# sb-sonata-led.net
KiCad netlist of a schematic drawn in Altium Designer
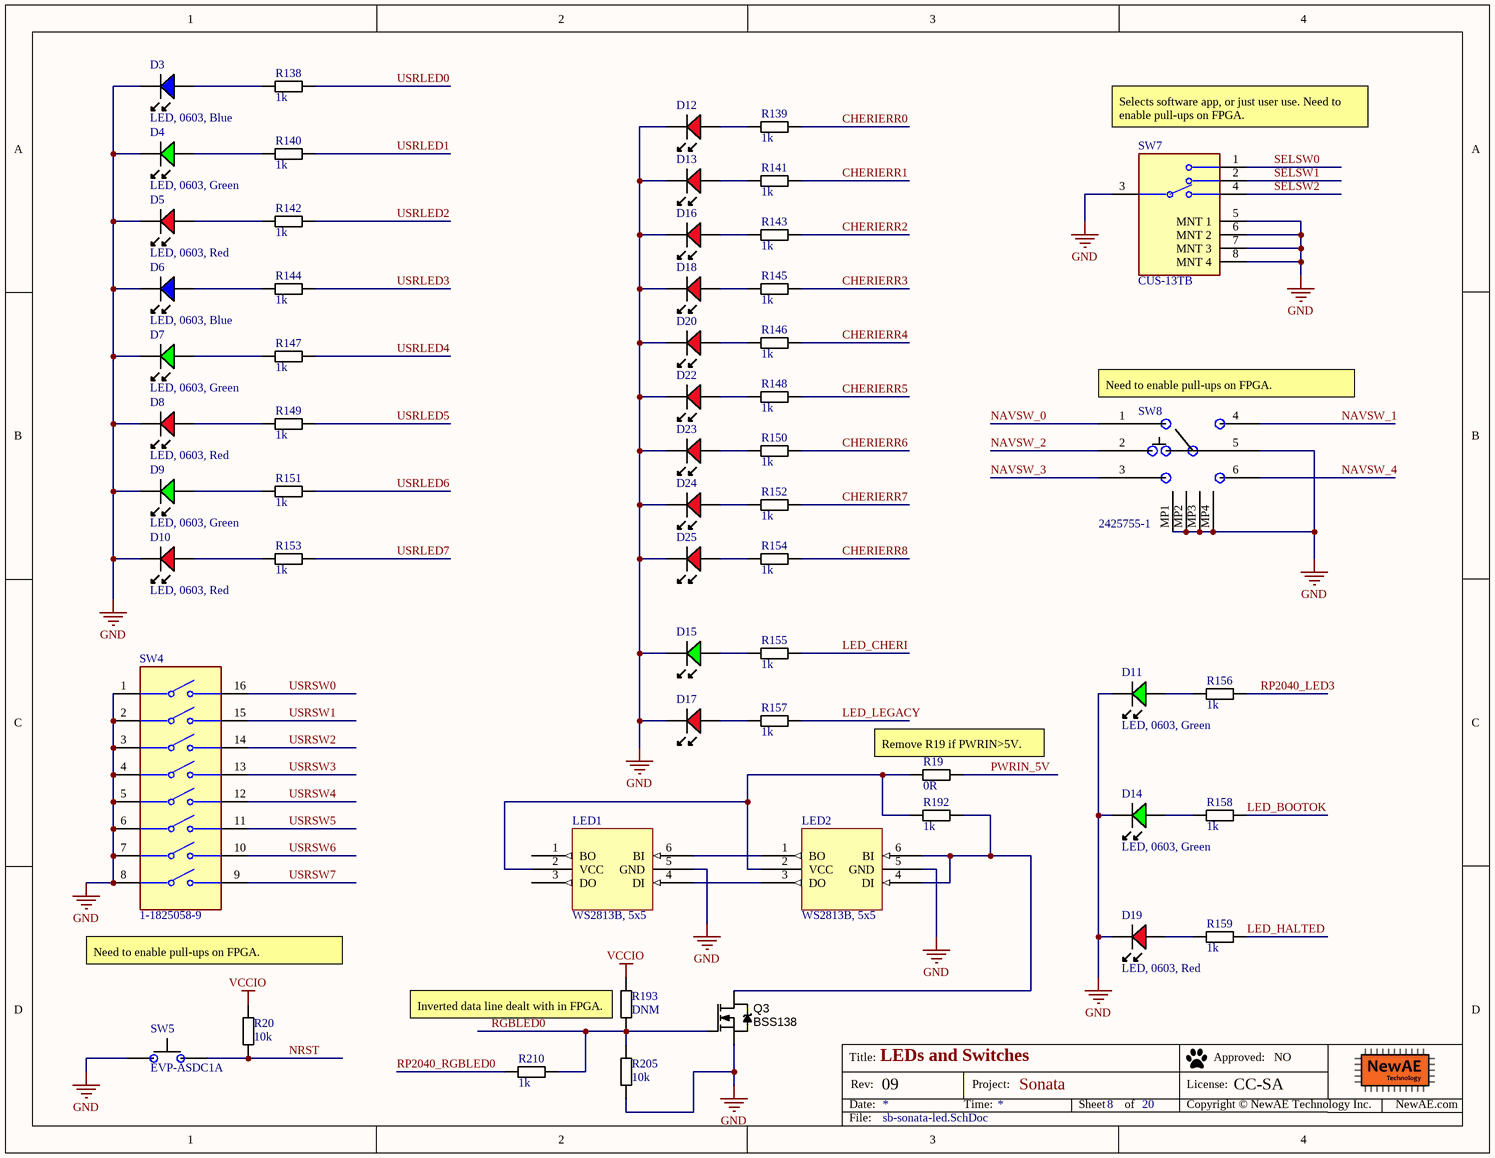
[diagram p0: sb-sonata-led.SchDoc]

(export (version "E")
  (design (tool "Eeschema 10.0.6"))
  (components
    (comp (ref "D3")
      (value "LED, 0603, Blue")
      (footprint "LED-0603-BLUE")
      (description "Chip LED, Blue")
      (fields (field (name "PART NUMBER") "LEDCHIP_0603_BLUE"))
      (libsource (lib "NewAE_AltiumLib") (part "LED_BLUE"))
    )
    (comp (ref "D4")
      (value "LED, 0603, Green")
      (footprint "LED-0603-GREEN")
      (description "Chip LED, Green")
      (fields (field (name "PART NUMBER") "LEDCHIP_0603_GREEN"))
      (libsource (lib "NewAE_AltiumLib") (part "LED_GREEN"))
    )
    (comp (ref "D5")
      (value "LED, 0603, Red")
      (footprint "LED-0603-RED")
      (description "Chip LED, Red")
      (fields (field (name "PART NUMBER") "LEDCHIP_0603_RED"))
      (libsource (lib "NewAE_AltiumLib") (part "LED_RED"))
    )
    (comp (ref "D6")
      (value "LED, 0603, Blue")
      (footprint "LED-0603-BLUE")
      (description "Chip LED, Blue")
      (fields (field (name "PART NUMBER") "LEDCHIP_0603_BLUE"))
      (libsource (lib "NewAE_AltiumLib") (part "LED_BLUE"))
    )
    (comp (ref "D7")
      (value "LED, 0603, Green")
      (footprint "LED-0603-GREEN")
      (description "Chip LED, Green")
      (fields (field (name "PART NUMBER") "LEDCHIP_0603_GREEN"))
      (libsource (lib "NewAE_AltiumLib") (part "LED_GREEN"))
    )
    (comp (ref "D8")
      (value "LED, 0603, Red")
      (footprint "LED-0603-RED")
      (description "Chip LED, Red")
      (fields (field (name "PART NUMBER") "LEDCHIP_0603_RED"))
      (libsource (lib "NewAE_AltiumLib") (part "LED_RED"))
    )
    (comp (ref "D9")
      (value "LED, 0603, Green")
      (footprint "LED-0603-GREEN")
      (description "Chip LED, Green")
      (fields (field (name "PART NUMBER") "LEDCHIP_0603_GREEN"))
      (libsource (lib "NewAE_AltiumLib") (part "LED_GREEN"))
    )
    (comp (ref "D10")
      (value "LED, 0603, Red")
      (footprint "LED-0603-RED")
      (description "Chip LED, Red")
      (fields (field (name "PART NUMBER") "LEDCHIP_0603_RED"))
      (libsource (lib "NewAE_AltiumLib") (part "LED_RED"))
    )
    (comp (ref "D11")
      (value "LED, 0603, Green")
      (footprint "LED-0603-GREEN")
      (description "Chip LED, Green")
      (fields (field (name "PART NUMBER") "LEDCHIP_0603_GREEN"))
      (libsource (lib "NewAE_AltiumLib") (part "LED_GREEN"))
    )
    (comp (ref "D12")
      (value "LED, 0603, Red")
      (footprint "LED-0603-RED")
      (description "Chip LED, Red")
      (fields (field (name "PART NUMBER") "LEDCHIP_0603_RED"))
      (libsource (lib "NewAE_AltiumLib") (part "LED_RED"))
    )
    (comp (ref "D13")
      (value "LED, 0603, Red")
      (footprint "LED-0603-RED")
      (description "Chip LED, Red")
      (fields (field (name "PART NUMBER") "LEDCHIP_0603_RED"))
      (libsource (lib "NewAE_AltiumLib") (part "LED_RED"))
    )
    (comp (ref "D14")
      (value "LED, 0603, Green")
      (footprint "LED-0603-GREEN")
      (description "Chip LED, Green")
      (fields (field (name "PART NUMBER") "LEDCHIP_0603_GREEN"))
      (libsource (lib "NewAE_AltiumLib") (part "LED_GREEN"))
    )
    (comp (ref "D15")
      (value "LED, 0603, Green")
      (footprint "LED-0603-GREEN")
      (description "Chip LED, Green")
      (fields (field (name "PART NUMBER") "LEDCHIP_0603_GREEN"))
      (libsource (lib "NewAE_AltiumLib") (part "LED_GREEN"))
    )
    (comp (ref "D16")
      (value "LED, 0603, Red")
      (footprint "LED-0603-RED")
      (description "Chip LED, Red")
      (fields (field (name "PART NUMBER") "LEDCHIP_0603_RED"))
      (libsource (lib "NewAE_AltiumLib") (part "LED_RED"))
    )
    (comp (ref "D17")
      (value "LED, 0603, Red")
      (footprint "LED-0603-RED")
      (description "Chip LED, Red")
      (fields (field (name "PART NUMBER") "LEDCHIP_0603_RED"))
      (libsource (lib "NewAE_AltiumLib") (part "LED_RED"))
    )
    (comp (ref "D18")
      (value "LED, 0603, Red")
      (footprint "LED-0603-RED")
      (description "Chip LED, Red")
      (fields (field (name "PART NUMBER") "LEDCHIP_0603_RED"))
      (libsource (lib "NewAE_AltiumLib") (part "LED_RED"))
    )
    (comp (ref "D19")
      (value "LED, 0603, Red")
      (footprint "LED-0603-RED")
      (description "Chip LED, Red")
      (fields (field (name "PART NUMBER") "LEDCHIP_0603_RED"))
      (libsource (lib "NewAE_AltiumLib") (part "LED_RED"))
    )
    (comp (ref "D20")
      (value "LED, 0603, Red")
      (footprint "LED-0603-RED")
      (description "Chip LED, Red")
      (fields (field (name "PART NUMBER") "LEDCHIP_0603_RED"))
      (libsource (lib "NewAE_AltiumLib") (part "LED_RED"))
    )
    (comp (ref "D22")
      (value "LED, 0603, Red")
      (footprint "LED-0603-RED")
      (description "Chip LED, Red")
      (fields (field (name "PART NUMBER") "LEDCHIP_0603_RED"))
      (libsource (lib "NewAE_AltiumLib") (part "LED_RED"))
    )
    (comp (ref "D23")
      (value "LED, 0603, Red")
      (footprint "LED-0603-RED")
      (description "Chip LED, Red")
      (fields (field (name "PART NUMBER") "LEDCHIP_0603_RED"))
      (libsource (lib "NewAE_AltiumLib") (part "LED_RED"))
    )
    (comp (ref "D24")
      (value "LED, 0603, Red")
      (footprint "LED-0603-RED")
      (description "Chip LED, Red")
      (fields (field (name "PART NUMBER") "LEDCHIP_0603_RED"))
      (libsource (lib "NewAE_AltiumLib") (part "LED_RED"))
    )
    (comp (ref "D25")
      (value "LED, 0603, Red")
      (footprint "LED-0603-RED")
      (description "Chip LED, Red")
      (fields (field (name "PART NUMBER") "LEDCHIP_0603_RED"))
      (libsource (lib "NewAE_AltiumLib") (part "LED_RED"))
    )
    (comp (ref "LED1")
      (value "WS2813B, 5x5")
      (footprint "WS2813B_5x5")
      (description "WS2813B, 5x5 SMD Neopixel")
      (fields (field (name "PART NUMBER") "WS2813B_5x5"))
      (libsource (lib "NewAE_AltiumLib") (part "WS2813B"))
    )
    (comp (ref "LED2")
      (value "WS2813B, 5x5")
      (footprint "WS2813B_5x5")
      (description "WS2813B, 5x5 SMD Neopixel")
      (fields (field (name "PART NUMBER") "WS2813B_5x5"))
      (libsource (lib "NewAE_AltiumLib") (part "WS2813B"))
    )
    (comp (ref "Q3")
      (value "BSS138")
      (footprint "SOT95P245X110-3M")
      (description "MOSFET N-CH 30V 2.2A SOT23-3")
      (libsource (lib "NewAE_AltiumLib") (part "MOSFET_N_GSD"))
    )
    (comp (ref "R19")
      (value "0R")
      (footprint "RESC1608X55N")
      (description "0R, 0603, 1/10W")
      (fields (field (name "PART NUMBER") "RCHIP-0R-0603") (field (name "TOLERANCE") "1%"))
      (libsource (lib "") (part "RES-EU_2"))
    )
    (comp (ref "R20")
      (value "10k")
      (footprint "RESC1005X40N")
      (description "10k res, 0402, 1%, 1/16W")
      (fields (field (name "PART NUMBER") "RCHIP-10K-0402") (field (name "TOLERANCE") "1%"))
      (libsource (lib "") (part "RES-EU_1"))
    )
    (comp (ref "R138")
      (value "1k")
      (footprint "RESC1005X40N")
      (description "1k res, 0402, 1%, 1/16W")
      (fields (field (name "PART NUMBER") "RCHIP-1K-0402") (field (name "TOLERANCE") "1%"))
      (libsource (lib "NewAE_AltiumLib") (part "RES-EU"))
    )
    (comp (ref "R139")
      (value "1k")
      (footprint "RESC1005X40N")
      (description "1k res, 0402, 1%, 1/16W")
      (fields (field (name "PART NUMBER") "RCHIP-1K-0402") (field (name "TOLERANCE") "1%"))
      (libsource (lib "NewAE_AltiumLib") (part "RES-EU"))
    )
    (comp (ref "R140")
      (value "1k")
      (footprint "RESC1005X40N")
      (description "1k res, 0402, 1%, 1/16W")
      (fields (field (name "PART NUMBER") "RCHIP-1K-0402") (field (name "TOLERANCE") "1%"))
      (libsource (lib "NewAE_AltiumLib") (part "RES-EU"))
    )
    (comp (ref "R141")
      (value "1k")
      (footprint "RESC1005X40N")
      (description "1k res, 0402, 1%, 1/16W")
      (fields (field (name "PART NUMBER") "RCHIP-1K-0402") (field (name "TOLERANCE") "1%"))
      (libsource (lib "NewAE_AltiumLib") (part "RES-EU"))
    )
    (comp (ref "R142")
      (value "1k")
      (footprint "RESC1005X40N")
      (description "1k res, 0402, 1%, 1/16W")
      (fields (field (name "PART NUMBER") "RCHIP-1K-0402") (field (name "TOLERANCE") "1%"))
      (libsource (lib "NewAE_AltiumLib") (part "RES-EU"))
    )
    (comp (ref "R143")
      (value "1k")
      (footprint "RESC1005X40N")
      (description "1k res, 0402, 1%, 1/16W")
      (fields (field (name "PART NUMBER") "RCHIP-1K-0402") (field (name "TOLERANCE") "1%"))
      (libsource (lib "NewAE_AltiumLib") (part "RES-EU"))
    )
    (comp (ref "R144")
      (value "1k")
      (footprint "RESC1005X40N")
      (description "1k res, 0402, 1%, 1/16W")
      (fields (field (name "PART NUMBER") "RCHIP-1K-0402") (field (name "TOLERANCE") "1%"))
      (libsource (lib "NewAE_AltiumLib") (part "RES-EU"))
    )
    (comp (ref "R145")
      (value "1k")
      (footprint "RESC1005X40N")
      (description "1k res, 0402, 1%, 1/16W")
      (fields (field (name "PART NUMBER") "RCHIP-1K-0402") (field (name "TOLERANCE") "1%"))
      (libsource (lib "NewAE_AltiumLib") (part "RES-EU"))
    )
    (comp (ref "R146")
      (value "1k")
      (footprint "RESC1005X40N")
      (description "1k res, 0402, 1%, 1/16W")
      (fields (field (name "PART NUMBER") "RCHIP-1K-0402") (field (name "TOLERANCE") "1%"))
      (libsource (lib "NewAE_AltiumLib") (part "RES-EU"))
    )
    (comp (ref "R147")
      (value "1k")
      (footprint "RESC1005X40N")
      (description "1k res, 0402, 1%, 1/16W")
      (fields (field (name "PART NUMBER") "RCHIP-1K-0402") (field (name "TOLERANCE") "1%"))
      (libsource (lib "NewAE_AltiumLib") (part "RES-EU"))
    )
    (comp (ref "R148")
      (value "1k")
      (footprint "RESC1005X40N")
      (description "1k res, 0402, 1%, 1/16W")
      (fields (field (name "PART NUMBER") "RCHIP-1K-0402") (field (name "TOLERANCE") "1%"))
      (libsource (lib "NewAE_AltiumLib") (part "RES-EU"))
    )
    (comp (ref "R149")
      (value "1k")
      (footprint "RESC1005X40N")
      (description "1k res, 0402, 1%, 1/16W")
      (fields (field (name "PART NUMBER") "RCHIP-1K-0402") (field (name "TOLERANCE") "1%"))
      (libsource (lib "NewAE_AltiumLib") (part "RES-EU"))
    )
    (comp (ref "R150")
      (value "1k")
      (footprint "RESC1005X40N")
      (description "1k res, 0402, 1%, 1/16W")
      (fields (field (name "PART NUMBER") "RCHIP-1K-0402") (field (name "TOLERANCE") "1%"))
      (libsource (lib "NewAE_AltiumLib") (part "RES-EU"))
    )
    (comp (ref "R151")
      (value "1k")
      (footprint "RESC1005X40N")
      (description "1k res, 0402, 1%, 1/16W")
      (fields (field (name "PART NUMBER") "RCHIP-1K-0402") (field (name "TOLERANCE") "1%"))
      (libsource (lib "NewAE_AltiumLib") (part "RES-EU"))
    )
    (comp (ref "R152")
      (value "1k")
      (footprint "RESC1005X40N")
      (description "1k res, 0402, 1%, 1/16W")
      (fields (field (name "PART NUMBER") "RCHIP-1K-0402") (field (name "TOLERANCE") "1%"))
      (libsource (lib "NewAE_AltiumLib") (part "RES-EU"))
    )
    (comp (ref "R153")
      (value "1k")
      (footprint "RESC1005X40N")
      (description "1k res, 0402, 1%, 1/16W")
      (fields (field (name "PART NUMBER") "RCHIP-1K-0402") (field (name "TOLERANCE") "1%"))
      (libsource (lib "NewAE_AltiumLib") (part "RES-EU"))
    )
    (comp (ref "R154")
      (value "1k")
      (footprint "RESC1005X40N")
      (description "1k res, 0402, 1%, 1/16W")
      (fields (field (name "PART NUMBER") "RCHIP-1K-0402") (field (name "TOLERANCE") "1%"))
      (libsource (lib "NewAE_AltiumLib") (part "RES-EU"))
    )
    (comp (ref "R155")
      (value "1k")
      (footprint "RESC1005X40N")
      (description "1k res, 0402, 1%, 1/16W")
      (fields (field (name "PART NUMBER") "RCHIP-1K-0402") (field (name "TOLERANCE") "1%"))
      (libsource (lib "NewAE_AltiumLib") (part "RES-EU"))
    )
    (comp (ref "R156")
      (value "1k")
      (footprint "RESC1005X40N")
      (description "1k res, 0402, 1%, 1/16W")
      (fields (field (name "PART NUMBER") "RCHIP-1K-0402") (field (name "TOLERANCE") "1%"))
      (libsource (lib "NewAE_AltiumLib") (part "RES-EU"))
    )
    (comp (ref "R157")
      (value "1k")
      (footprint "RESC1005X40N")
      (description "1k res, 0402, 1%, 1/16W")
      (fields (field (name "PART NUMBER") "RCHIP-1K-0402") (field (name "TOLERANCE") "1%"))
      (libsource (lib "NewAE_AltiumLib") (part "RES-EU"))
    )
    (comp (ref "R158")
      (value "1k")
      (footprint "RESC1005X40N")
      (description "1k res, 0402, 1%, 1/16W")
      (fields (field (name "PART NUMBER") "RCHIP-1K-0402") (field (name "TOLERANCE") "1%"))
      (libsource (lib "NewAE_AltiumLib") (part "RES-EU"))
    )
    (comp (ref "R159")
      (value "1k")
      (footprint "RESC1005X40N")
      (description "1k res, 0402, 1%, 1/16W")
      (fields (field (name "PART NUMBER") "RCHIP-1K-0402") (field (name "TOLERANCE") "1%"))
      (libsource (lib "NewAE_AltiumLib") (part "RES-EU"))
    )
    (comp (ref "R192")
      (value "1k")
      (footprint "RESC1005X40N")
      (description "1k res, 0402, 1%, 1/16W")
      (fields (field (name "PART NUMBER") "RCHIP-1K-0402") (field (name "TOLERANCE") "1%"))
      (libsource (lib "") (part "RES-EU_2"))
    )
    (comp (ref "R193")
      (value "DNM")
      (footprint "RESC1005X40N")
      (fields (field (name "PART NUMBER") "RCHIP-DNM-0402"))
      (libsource (lib "") (part "RES-EU_1"))
    )
    (comp (ref "R205")
      (value "10k")
      (footprint "RESC1005X40N")
      (description "10k res, 0402, 1%, 1/16W")
      (fields (field (name "PART NUMBER") "RCHIP-10K-0402") (field (name "TOLERANCE") "1%"))
      (libsource (lib "") (part "RES-EU_1"))
    )
    (comp (ref "R210")
      (value "1k")
      (footprint "RESC1005X40N")
      (description "1k res, 0402, 1%, 1/16W")
      (fields (field (name "PART NUMBER") "RCHIP-1K-0402") (field (name "TOLERANCE") "1%"))
      (libsource (lib "NewAE_AltiumLib") (part "RES-EU"))
    )
    (comp (ref "SW4")
      (value "1-1825058-9")
      (footprint "FP-1-1825058-9-MFG")
      (description "SWITCH SLIDE DIP SPST 100MA 24V")
      (fields
        (field (name "MANUFACTURER") "TE Connectivity")
        (field (name "OCTOPART") "https://octopart.com/1-1825058-9-te+connectivity-46507285")
      )
      (libsource (lib "Altium Content Vault") (part "88b473189f0daa5e8e83a09a3141fee"))
    )
    (comp (ref "SW5")
      (value "EVP-ASDC1A")
      (footprint "EVPAS")
      (description "Pushbutton, SMD, 2.5NM force, NO")
      (libsource (lib "NewAE_AltiumLib") (part "SW_PB_NO_2PIN"))
    )
    (comp (ref "SW7")
      (value "CUS-13TB")
      (footprint "FP-CUS-13TB-MFG")
      (description "SWITCH SLIDE SP3T 300MA 4V")
      (libsource (lib "Altium Content Vault") (part "47bcb96ef67674530f45e4053201745"))
    )
    (comp (ref "SW8")
      (value "2425755-1")
      (footprint "2425755-1")
      (description "5-Way Joystick")
      (libsource (lib "NewAE_AltiumLib") (part "SW_5WAY_4MP"))
    )
  )
  (nets
    (net (code "1") (name "/CHERIERR0") (class "Default")
      (node (ref "R139") (pin "1") (pinfunction "1_1") (pintype "passive"))
    )
    (net (code "2") (name "/CHERIERR1") (class "Default")
      (node (ref "R141") (pin "1") (pinfunction "1_1") (pintype "passive"))
    )
    (net (code "3") (name "/CHERIERR2") (class "Default")
      (node (ref "R143") (pin "1") (pinfunction "1_1") (pintype "passive"))
    )
    (net (code "4") (name "/CHERIERR3") (class "Default")
      (node (ref "R145") (pin "1") (pinfunction "1_1") (pintype "passive"))
    )
    (net (code "5") (name "/CHERIERR4") (class "Default")
      (node (ref "R146") (pin "1") (pinfunction "1_1") (pintype "passive"))
    )
    (net (code "6") (name "/CHERIERR5") (class "Default")
      (node (ref "R148") (pin "1") (pinfunction "1_1") (pintype "passive"))
    )
    (net (code "7") (name "/CHERIERR6") (class "Default")
      (node (ref "R150") (pin "1") (pinfunction "1_1") (pintype "passive"))
    )
    (net (code "8") (name "/CHERIERR7") (class "Default")
      (node (ref "R152") (pin "1") (pinfunction "1_1") (pintype "passive"))
    )
    (net (code "9") (name "/CHERIERR8") (class "Default")
      (node (ref "R154") (pin "1") (pinfunction "1_1") (pintype "passive"))
    )
    (net (code "10") (name "/LED_BOOTOK") (class "Default")
      (node (ref "R158") (pin "1") (pinfunction "1_1") (pintype "passive"))
    )
    (net (code "11") (name "/LED_CHERI") (class "Default")
      (node (ref "R155") (pin "1") (pinfunction "1_1") (pintype "passive"))
    )
    (net (code "12") (name "/LED_HALTED") (class "Default")
      (node (ref "R159") (pin "1") (pinfunction "1_1") (pintype "passive"))
    )
    (net (code "13") (name "/LED_LEGACY") (class "Default")
      (node (ref "R157") (pin "1") (pinfunction "1_1") (pintype "passive"))
    )
    (net (code "14") (name "/NAVSW_0") (class "Default")
      (node (ref "SW8") (pin "1") (pinfunction "1_1") (pintype "passive"))
    )
    (net (code "15") (name "/NAVSW_1") (class "Default")
      (node (ref "SW8") (pin "4") (pinfunction "4_4") (pintype "passive"))
    )
    (net (code "16") (name "/NAVSW_2") (class "Default")
      (node (ref "SW8") (pin "2") (pinfunction "2_2") (pintype "passive"))
    )
    (net (code "17") (name "/NAVSW_3") (class "Default")
      (node (ref "SW8") (pin "3") (pinfunction "3_3") (pintype "passive"))
    )
    (net (code "18") (name "/NAVSW_4") (class "Default")
      (node (ref "SW8") (pin "6") (pinfunction "6_6") (pintype "passive"))
    )
    (net (code "19") (name "/NRST") (class "Default")
      (node (ref "R20") (pin "2") (pinfunction "2_2") (pintype "passive"))
      (node (ref "SW5") (pin "2") (pinfunction "IN_2") (pintype "passive"))
    )
    (net (code "20") (name "/PWRIN_5V") (class "Default")
      (node (ref "R19") (pin "2") (pinfunction "2_2") (pintype "passive"))
    )
    (net (code "21") (name "/RGBLED0") (class "Default")
      (node (ref "Q3") (pin "1") (pinfunction "G_1") (pintype "passive"))
      (node (ref "R193") (pin "2") (pinfunction "2_2") (pintype "passive"))
      (node (ref "R205") (pin "1") (pinfunction "1_1") (pintype "passive"))
      (node (ref "R210") (pin "1") (pinfunction "1_1") (pintype "passive"))
    )
    (net (code "22") (name "/RP2040_LED3") (class "Default")
      (node (ref "R156") (pin "1") (pinfunction "1_1") (pintype "passive"))
    )
    (net (code "23") (name "/RP2040_RGBLED0") (class "Default")
      (node (ref "R210") (pin "2") (pinfunction "2_2") (pintype "passive"))
    )
    (net (code "24") (name "/SELSW0") (class "Default")
      (node (ref "SW7") (pin "1") (pinfunction "1_1") (pintype "passive"))
    )
    (net (code "25") (name "/SELSW1") (class "Default")
      (node (ref "SW7") (pin "2") (pinfunction "2_2") (pintype "passive"))
    )
    (net (code "26") (name "/SELSW2") (class "Default")
      (node (ref "SW7") (pin "4") (pinfunction "4_4") (pintype "passive"))
    )
    (net (code "27") (name "/USRLED0") (class "Default")
      (node (ref "R138") (pin "1") (pinfunction "1_1") (pintype "passive"))
    )
    (net (code "28") (name "/USRLED1") (class "Default")
      (node (ref "R140") (pin "1") (pinfunction "1_1") (pintype "passive"))
    )
    (net (code "29") (name "/USRLED2") (class "Default")
      (node (ref "R142") (pin "1") (pinfunction "1_1") (pintype "passive"))
    )
    (net (code "30") (name "/USRLED3") (class "Default")
      (node (ref "R144") (pin "1") (pinfunction "1_1") (pintype "passive"))
    )
    (net (code "31") (name "/USRLED4") (class "Default")
      (node (ref "R147") (pin "1") (pinfunction "1_1") (pintype "passive"))
    )
    (net (code "32") (name "/USRLED5") (class "Default")
      (node (ref "R149") (pin "1") (pinfunction "1_1") (pintype "passive"))
    )
    (net (code "33") (name "/USRLED6") (class "Default")
      (node (ref "R151") (pin "1") (pinfunction "1_1") (pintype "passive"))
    )
    (net (code "34") (name "/USRLED7") (class "Default")
      (node (ref "R153") (pin "1") (pinfunction "1_1") (pintype "passive"))
    )
    (net (code "35") (name "/USRSW0") (class "Default")
      (node (ref "SW4") (pin "16") (pinfunction "16_16") (pintype "passive"))
    )
    (net (code "36") (name "/USRSW1") (class "Default")
      (node (ref "SW4") (pin "15") (pinfunction "15_15") (pintype "passive"))
    )
    (net (code "37") (name "/USRSW2") (class "Default")
      (node (ref "SW4") (pin "14") (pinfunction "14_14") (pintype "passive"))
    )
    (net (code "38") (name "/USRSW3") (class "Default")
      (node (ref "SW4") (pin "13") (pinfunction "13_13") (pintype "passive"))
    )
    (net (code "39") (name "/USRSW4") (class "Default")
      (node (ref "SW4") (pin "12") (pinfunction "12_12") (pintype "passive"))
    )
    (net (code "40") (name "/USRSW5") (class "Default")
      (node (ref "SW4") (pin "11") (pinfunction "11_11") (pintype "passive"))
    )
    (net (code "41") (name "/USRSW6") (class "Default")
      (node (ref "SW4") (pin "10") (pinfunction "10_10") (pintype "passive"))
    )
    (net (code "42") (name "/USRSW7") (class "Default")
      (node (ref "SW4") (pin "9") (pinfunction "9_9") (pintype "passive"))
    )
    (net (code "43") (name "GND") (class "Default")
      (node (ref "D10") (pin "K") (pinfunction "K_K") (pintype "passive"))
      (node (ref "D11") (pin "K") (pinfunction "K_K") (pintype "passive"))
      (node (ref "D12") (pin "K") (pinfunction "K_K") (pintype "passive"))
      (node (ref "D13") (pin "K") (pinfunction "K_K") (pintype "passive"))
      (node (ref "D14") (pin "K") (pinfunction "K_K") (pintype "passive"))
      (node (ref "D15") (pin "K") (pinfunction "K_K") (pintype "passive"))
      (node (ref "D16") (pin "K") (pinfunction "K_K") (pintype "passive"))
      (node (ref "D17") (pin "K") (pinfunction "K_K") (pintype "passive"))
      (node (ref "D18") (pin "K") (pinfunction "K_K") (pintype "passive"))
      (node (ref "D19") (pin "K") (pinfunction "K_K") (pintype "passive"))
      (node (ref "D20") (pin "K") (pinfunction "K_K") (pintype "passive"))
      (node (ref "D22") (pin "K") (pinfunction "K_K") (pintype "passive"))
      (node (ref "D23") (pin "K") (pinfunction "K_K") (pintype "passive"))
      (node (ref "D24") (pin "K") (pinfunction "K_K") (pintype "passive"))
      (node (ref "D25") (pin "K") (pinfunction "K_K") (pintype "passive"))
      (node (ref "D3") (pin "K") (pinfunction "K_K") (pintype "passive"))
      (node (ref "D4") (pin "K") (pinfunction "K_K") (pintype "passive"))
      (node (ref "D5") (pin "K") (pinfunction "K_K") (pintype "passive"))
      (node (ref "D6") (pin "K") (pinfunction "K_K") (pintype "passive"))
      (node (ref "D7") (pin "K") (pinfunction "K_K") (pintype "passive"))
      (node (ref "D8") (pin "K") (pinfunction "K_K") (pintype "passive"))
      (node (ref "D9") (pin "K") (pinfunction "K_K") (pintype "passive"))
      (node (ref "LED1") (pin "5") (pinfunction "GND_5") (pintype "passive"))
      (node (ref "LED2") (pin "5") (pinfunction "GND_5") (pintype "passive"))
      (node (ref "Q3") (pin "2") (pinfunction "S_2") (pintype "passive"))
      (node (ref "R205") (pin "2") (pinfunction "2_2") (pintype "passive"))
      (node (ref "SW4") (pin "1") (pinfunction "1_1") (pintype "passive"))
      (node (ref "SW4") (pin "2") (pinfunction "2_2") (pintype "passive"))
      (node (ref "SW4") (pin "3") (pinfunction "3_3") (pintype "passive"))
      (node (ref "SW4") (pin "4") (pinfunction "4_4") (pintype "passive"))
      (node (ref "SW4") (pin "5") (pinfunction "5_5") (pintype "passive"))
      (node (ref "SW4") (pin "6") (pinfunction "6_6") (pintype "passive"))
      (node (ref "SW4") (pin "7") (pinfunction "7_7") (pintype "passive"))
      (node (ref "SW4") (pin "8") (pinfunction "8_8") (pintype "passive"))
      (node (ref "SW5") (pin "1") (pinfunction "IN_1") (pintype "passive"))
      (node (ref "SW7") (pin "3") (pinfunction "C_3") (pintype "passive"))
      (node (ref "SW7") (pin "5") (pinfunction "MNT_1_5") (pintype "passive"))
      (node (ref "SW7") (pin "6") (pinfunction "MNT_2_6") (pintype "passive"))
      (node (ref "SW7") (pin "7") (pinfunction "MNT_3_7") (pintype "passive"))
      (node (ref "SW7") (pin "8") (pinfunction "MNT_4_8") (pintype "passive"))
      (node (ref "SW8") (pin "5") (pinfunction "5_5") (pintype "passive"))
      (node (ref "SW8") (pin "MP1") (pinfunction "MP1_MP1") (pintype "passive"))
      (node (ref "SW8") (pin "MP2") (pinfunction "MP2_MP2") (pintype "passive"))
      (node (ref "SW8") (pin "MP3") (pinfunction "MP3_MP3") (pintype "passive"))
      (node (ref "SW8") (pin "MP4") (pinfunction "MP4_MP4") (pintype "passive"))
    )
    (net (code "44") (name "Net-(D3-PadA)") (class "Default")
      (node (ref "D3") (pin "A") (pinfunction "A_A") (pintype "passive"))
      (node (ref "R138") (pin "2") (pinfunction "2_2") (pintype "passive"))
    )
    (net (code "45") (name "Net-(D4-PadA)") (class "Default")
      (node (ref "D4") (pin "A") (pinfunction "A_A") (pintype "passive"))
      (node (ref "R140") (pin "2") (pinfunction "2_2") (pintype "passive"))
    )
    (net (code "46") (name "Net-(D5-PadA)") (class "Default")
      (node (ref "D5") (pin "A") (pinfunction "A_A") (pintype "passive"))
      (node (ref "R142") (pin "2") (pinfunction "2_2") (pintype "passive"))
    )
    (net (code "47") (name "Net-(D6-PadA)") (class "Default")
      (node (ref "D6") (pin "A") (pinfunction "A_A") (pintype "passive"))
      (node (ref "R144") (pin "2") (pinfunction "2_2") (pintype "passive"))
    )
    (net (code "48") (name "Net-(D7-PadA)") (class "Default")
      (node (ref "D7") (pin "A") (pinfunction "A_A") (pintype "passive"))
      (node (ref "R147") (pin "2") (pinfunction "2_2") (pintype "passive"))
    )
    (net (code "49") (name "Net-(D8-PadA)") (class "Default")
      (node (ref "D8") (pin "A") (pinfunction "A_A") (pintype "passive"))
      (node (ref "R149") (pin "2") (pinfunction "2_2") (pintype "passive"))
    )
    (net (code "50") (name "Net-(D9-PadA)") (class "Default")
      (node (ref "D9") (pin "A") (pinfunction "A_A") (pintype "passive"))
      (node (ref "R151") (pin "2") (pinfunction "2_2") (pintype "passive"))
    )
    (net (code "51") (name "Net-(D10-PadA)") (class "Default")
      (node (ref "D10") (pin "A") (pinfunction "A_A") (pintype "passive"))
      (node (ref "R153") (pin "2") (pinfunction "2_2") (pintype "passive"))
    )
    (net (code "52") (name "Net-(D11-PadA)") (class "Default")
      (node (ref "D11") (pin "A") (pinfunction "A_A") (pintype "passive"))
      (node (ref "R156") (pin "2") (pinfunction "2_2") (pintype "passive"))
    )
    (net (code "53") (name "Net-(D12-PadA)") (class "Default")
      (node (ref "D12") (pin "A") (pinfunction "A_A") (pintype "passive"))
      (node (ref "R139") (pin "2") (pinfunction "2_2") (pintype "passive"))
    )
    (net (code "54") (name "Net-(D13-PadA)") (class "Default")
      (node (ref "D13") (pin "A") (pinfunction "A_A") (pintype "passive"))
      (node (ref "R141") (pin "2") (pinfunction "2_2") (pintype "passive"))
    )
    (net (code "55") (name "Net-(D14-PadA)") (class "Default")
      (node (ref "D14") (pin "A") (pinfunction "A_A") (pintype "passive"))
      (node (ref "R158") (pin "2") (pinfunction "2_2") (pintype "passive"))
    )
    (net (code "56") (name "Net-(D15-PadA)") (class "Default")
      (node (ref "D15") (pin "A") (pinfunction "A_A") (pintype "passive"))
      (node (ref "R155") (pin "2") (pinfunction "2_2") (pintype "passive"))
    )
    (net (code "57") (name "Net-(D16-PadA)") (class "Default")
      (node (ref "D16") (pin "A") (pinfunction "A_A") (pintype "passive"))
      (node (ref "R143") (pin "2") (pinfunction "2_2") (pintype "passive"))
    )
    (net (code "58") (name "Net-(D17-PadA)") (class "Default")
      (node (ref "D17") (pin "A") (pinfunction "A_A") (pintype "passive"))
      (node (ref "R157") (pin "2") (pinfunction "2_2") (pintype "passive"))
    )
    (net (code "59") (name "Net-(D18-PadA)") (class "Default")
      (node (ref "D18") (pin "A") (pinfunction "A_A") (pintype "passive"))
      (node (ref "R145") (pin "2") (pinfunction "2_2") (pintype "passive"))
    )
    (net (code "60") (name "Net-(D19-PadA)") (class "Default")
      (node (ref "D19") (pin "A") (pinfunction "A_A") (pintype "passive"))
      (node (ref "R159") (pin "2") (pinfunction "2_2") (pintype "passive"))
    )
    (net (code "61") (name "Net-(D20-PadA)") (class "Default")
      (node (ref "D20") (pin "A") (pinfunction "A_A") (pintype "passive"))
      (node (ref "R146") (pin "2") (pinfunction "2_2") (pintype "passive"))
    )
    (net (code "62") (name "Net-(D22-PadA)") (class "Default")
      (node (ref "D22") (pin "A") (pinfunction "A_A") (pintype "passive"))
      (node (ref "R148") (pin "2") (pinfunction "2_2") (pintype "passive"))
    )
    (net (code "63") (name "Net-(D23-PadA)") (class "Default")
      (node (ref "D23") (pin "A") (pinfunction "A_A") (pintype "passive"))
      (node (ref "R150") (pin "2") (pinfunction "2_2") (pintype "passive"))
    )
    (net (code "64") (name "Net-(D24-PadA)") (class "Default")
      (node (ref "D24") (pin "A") (pinfunction "A_A") (pintype "passive"))
      (node (ref "R152") (pin "2") (pinfunction "2_2") (pintype "passive"))
    )
    (net (code "65") (name "Net-(D25-PadA)") (class "Default")
      (node (ref "D25") (pin "A") (pinfunction "A_A") (pintype "passive"))
      (node (ref "R154") (pin "2") (pinfunction "2_2") (pintype "passive"))
    )
    (net (code "66") (name "Net-(LED1-BI)") (class "Default")
      (node (ref "LED1") (pin "6") (pinfunction "BI_6") (pintype "input"))
      (node (ref "LED2") (pin "1") (pinfunction "BO_1") (pintype "output"))
    )
    (net (code "67") (name "Net-(LED1-DI)") (class "Default")
      (node (ref "LED1") (pin "4") (pinfunction "DI_4") (pintype "input"))
      (node (ref "LED2") (pin "3") (pinfunction "DO_3") (pintype "output"))
    )
    (net (code "68") (name "Net-(LED1-VCC)") (class "Default")
      (node (ref "LED1") (pin "2") (pinfunction "VCC_2") (pintype "passive"))
      (node (ref "LED2") (pin "2") (pinfunction "VCC_2") (pintype "passive"))
      (node (ref "R19") (pin "1") (pinfunction "1_1") (pintype "passive"))
      (node (ref "R192") (pin "1") (pinfunction "1_1") (pintype "passive"))
    )
    (net (code "69") (name "Net-(LED2-BI)") (class "Default")
      (node (ref "LED2") (pin "4") (pinfunction "DI_4") (pintype "input"))
      (node (ref "LED2") (pin "6") (pinfunction "BI_6") (pintype "input"))
      (node (ref "Q3") (pin "3") (pinfunction "D_3") (pintype "passive"))
      (node (ref "R192") (pin "2") (pinfunction "2_2") (pintype "passive"))
    )
    (net (code "70") (name "VCCIO") (class "Default")
      (node (ref "R193") (pin "1") (pinfunction "1_1") (pintype "passive"))
      (node (ref "R20") (pin "1") (pinfunction "1_1") (pintype "passive"))
    )
    (net (code "71") (name "unconnected-(LED1-BO-Pad1)") (class "Default")
      (node (ref "LED1") (pin "1") (pinfunction "BO_1") (pintype "output"))
    )
    (net (code "72") (name "unconnected-(LED1-DO-Pad3)") (class "Default")
      (node (ref "LED1") (pin "3") (pinfunction "DO_3") (pintype "output"))
    )
  )
)
